# RSD_M1_HELMET_UNIT_MCU_STOP_LIGHT_V2.net
KiCad netlist of a schematic drawn in Altium Designer
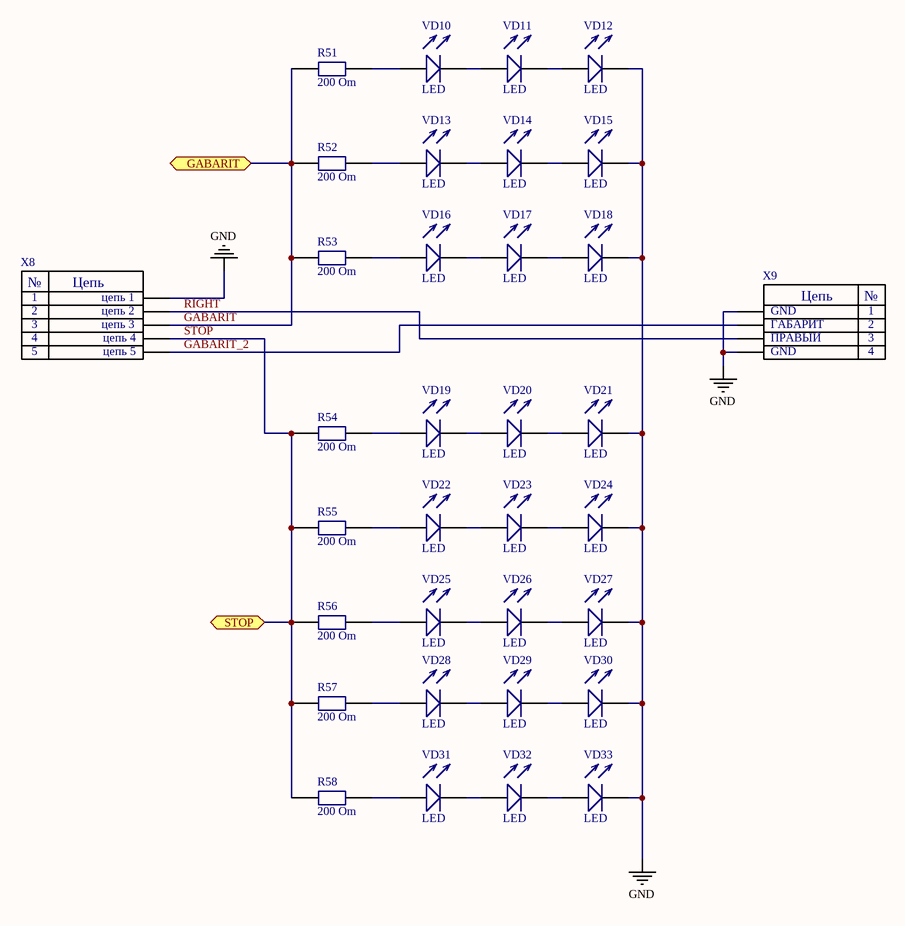
[diagram p0: RSD_M1_HELMET_UNIT_MCU_STOP_LIGHT_V2.SchDoc]

(export (version "E")
  (design (tool "Eeschema 10.0.6"))
  (components
    (comp (ref "R51")
      (value "200 Om")
      (footprint "Res0603")
      (fields (field (name "Comment") "Resistor"))
      (libsource (lib "my_library") (part "Resistor"))
    )
    (comp (ref "R52")
      (value "200 Om")
      (footprint "Res0603")
      (fields (field (name "Comment") "Resistor"))
      (libsource (lib "my_library") (part "Resistor"))
    )
    (comp (ref "R53")
      (value "200 Om")
      (footprint "Res0603")
      (fields (field (name "Comment") "Resistor"))
      (libsource (lib "my_library") (part "Resistor"))
    )
    (comp (ref "R54")
      (value "200 Om")
      (footprint "Res0603")
      (fields (field (name "Comment") "Resistor"))
      (libsource (lib "my_library") (part "Resistor"))
    )
    (comp (ref "R55")
      (value "200 Om")
      (footprint "Res0603")
      (fields (field (name "Comment") "Resistor"))
      (libsource (lib "my_library") (part "Resistor"))
    )
    (comp (ref "R56")
      (value "200 Om")
      (footprint "Res0603")
      (fields (field (name "Comment") "Resistor"))
      (libsource (lib "my_library") (part "Resistor"))
    )
    (comp (ref "R57")
      (value "200 Om")
      (footprint "Res0603")
      (fields (field (name "Comment") "Resistor"))
      (libsource (lib "my_library") (part "Resistor"))
    )
    (comp (ref "R58")
      (value "200 Om")
      (footprint "Res0603")
      (fields (field (name "Comment") "Resistor"))
      (libsource (lib "my_library") (part "Resistor"))
    )
    (comp (ref "VD10") (value "LED") (footprint "3528_LED") (libsource (lib "my_library") (part "LED")))
    (comp (ref "VD11") (value "LED") (footprint "3528_LED") (libsource (lib "my_library") (part "LED")))
    (comp (ref "VD12") (value "LED") (footprint "3528_LED") (libsource (lib "my_library") (part "LED")))
    (comp (ref "VD13") (value "LED") (footprint "3528_LED") (libsource (lib "my_library") (part "LED")))
    (comp (ref "VD14") (value "LED") (footprint "3528_LED") (libsource (lib "my_library") (part "LED")))
    (comp (ref "VD15") (value "LED") (footprint "3528_LED") (libsource (lib "my_library") (part "LED")))
    (comp (ref "VD16") (value "LED") (footprint "3528_LED") (libsource (lib "my_library") (part "LED")))
    (comp (ref "VD17") (value "LED") (footprint "3528_LED") (libsource (lib "my_library") (part "LED")))
    (comp (ref "VD18") (value "LED") (footprint "3528_LED") (libsource (lib "my_library") (part "LED")))
    (comp (ref "VD19") (value "LED") (footprint "3528_LED") (libsource (lib "my_library") (part "LED")))
    (comp (ref "VD20") (value "LED") (footprint "3528_LED") (libsource (lib "my_library") (part "LED")))
    (comp (ref "VD21") (value "LED") (footprint "3528_LED") (libsource (lib "my_library") (part "LED")))
    (comp (ref "VD22") (value "LED") (footprint "3528_LED") (libsource (lib "my_library") (part "LED")))
    (comp (ref "VD23") (value "LED") (footprint "3528_LED") (libsource (lib "my_library") (part "LED")))
    (comp (ref "VD24") (value "LED") (footprint "3528_LED") (libsource (lib "my_library") (part "LED")))
    (comp (ref "VD25") (value "LED") (footprint "3528_LED") (libsource (lib "my_library") (part "LED")))
    (comp (ref "VD26") (value "LED") (footprint "3528_LED") (libsource (lib "my_library") (part "LED")))
    (comp (ref "VD27") (value "LED") (footprint "3528_LED") (libsource (lib "my_library") (part "LED")))
    (comp (ref "VD28") (value "LED") (footprint "3528_LED") (libsource (lib "my_library") (part "LED")))
    (comp (ref "VD29") (value "LED") (footprint "3528_LED") (libsource (lib "my_library") (part "LED")))
    (comp (ref "VD30") (value "LED") (footprint "3528_LED") (libsource (lib "my_library") (part "LED")))
    (comp (ref "VD31") (value "LED") (footprint "3528_LED") (libsource (lib "my_library") (part "LED")))
    (comp (ref "VD32") (value "LED") (footprint "3528_LED") (libsource (lib "my_library") (part "LED")))
    (comp (ref "VD33") (value "LED") (footprint "3528_LED") (libsource (lib "my_library") (part "LED")))
    (comp (ref "X8")
      (value "FPC_connector_5_1")
      (footprint "FPC_5_1")
      (fields
        (field (name "1") "цепь 1")
        (field (name "2") "цепь 2")
        (field (name "3") "цепь 3")
        (field (name "4") "цепь 4")
        (field (name "5") "цепь 5")
      )
      (libsource (lib "my_library") (part "FPC_connector_5_1"))
    )
    (comp (ref "X9")
      (value "FPC_connector_4_1")
      (footprint "FPC_4_1")
      (fields
        (field (name "1") "GND")
        (field (name "2") "ГАБАРИТ")
        (field (name "3") "ПРАВЫЙ")
        (field (name "4") "GND")
      )
      (libsource (lib "my_library") (part "FPC_connector_4_1"))
    )
  )
  (nets
    (net (code "1") (name "/GABARIT") (class "Default")
      (node (ref "R51") (pin "2") (pinfunction "2_2") (pintype "passive"))
      (node (ref "R52") (pin "2") (pinfunction "2_2") (pintype "passive"))
      (node (ref "R53") (pin "2") (pinfunction "2_2") (pintype "passive"))
      (node (ref "X8") (pin "3") (pinfunction "3_3") (pintype "passive"))
    )
    (net (code "2") (name "/GABARIT_2") (class "Default")
      (node (ref "X8") (pin "5") (pinfunction "5_5") (pintype "passive"))
      (node (ref "X9") (pin "2") (pinfunction "2_2") (pintype "passive"))
    )
    (net (code "3") (name "/RIGHT") (class "Default")
      (node (ref "X8") (pin "2") (pinfunction "2_2") (pintype "passive"))
      (node (ref "X9") (pin "3") (pinfunction "3_3") (pintype "passive"))
    )
    (net (code "4") (name "/STOP") (class "Default")
      (node (ref "R54") (pin "2") (pinfunction "2_2") (pintype "passive"))
      (node (ref "R55") (pin "2") (pinfunction "2_2") (pintype "passive"))
      (node (ref "R56") (pin "2") (pinfunction "2_2") (pintype "passive"))
      (node (ref "R57") (pin "2") (pinfunction "2_2") (pintype "passive"))
      (node (ref "R58") (pin "2") (pinfunction "2_2") (pintype "passive"))
      (node (ref "X8") (pin "4") (pinfunction "4_4") (pintype "passive"))
    )
    (net (code "5") (name "GND") (class "Default")
      (node (ref "VD12") (pin "1") (pinfunction "1_1") (pintype "passive"))
      (node (ref "VD15") (pin "1") (pinfunction "1_1") (pintype "passive"))
      (node (ref "VD18") (pin "1") (pinfunction "1_1") (pintype "passive"))
      (node (ref "VD21") (pin "1") (pinfunction "1_1") (pintype "passive"))
      (node (ref "VD24") (pin "1") (pinfunction "1_1") (pintype "passive"))
      (node (ref "VD27") (pin "1") (pinfunction "1_1") (pintype "passive"))
      (node (ref "VD30") (pin "1") (pinfunction "1_1") (pintype "passive"))
      (node (ref "VD33") (pin "1") (pinfunction "1_1") (pintype "passive"))
      (node (ref "X8") (pin "1") (pinfunction "1_1") (pintype "passive"))
      (node (ref "X9") (pin "1") (pinfunction "1_1") (pintype "passive"))
      (node (ref "X9") (pin "4") (pinfunction "4_4") (pintype "passive"))
    )
    (net (code "6") (name "Net-(R51-Pad1)") (class "Default")
      (node (ref "R51") (pin "1") (pinfunction "1_1") (pintype "passive"))
      (node (ref "VD10") (pin "2") (pinfunction "2_2") (pintype "passive"))
    )
    (net (code "7") (name "Net-(R52-Pad1)") (class "Default")
      (node (ref "R52") (pin "1") (pinfunction "1_1") (pintype "passive"))
      (node (ref "VD13") (pin "2") (pinfunction "2_2") (pintype "passive"))
    )
    (net (code "8") (name "Net-(R53-Pad1)") (class "Default")
      (node (ref "R53") (pin "1") (pinfunction "1_1") (pintype "passive"))
      (node (ref "VD16") (pin "2") (pinfunction "2_2") (pintype "passive"))
    )
    (net (code "9") (name "Net-(R54-Pad1)") (class "Default")
      (node (ref "R54") (pin "1") (pinfunction "1_1") (pintype "passive"))
      (node (ref "VD19") (pin "2") (pinfunction "2_2") (pintype "passive"))
    )
    (net (code "10") (name "Net-(R55-Pad1)") (class "Default")
      (node (ref "R55") (pin "1") (pinfunction "1_1") (pintype "passive"))
      (node (ref "VD22") (pin "2") (pinfunction "2_2") (pintype "passive"))
    )
    (net (code "11") (name "Net-(R56-Pad1)") (class "Default")
      (node (ref "R56") (pin "1") (pinfunction "1_1") (pintype "passive"))
      (node (ref "VD25") (pin "2") (pinfunction "2_2") (pintype "passive"))
    )
    (net (code "12") (name "Net-(R57-Pad1)") (class "Default")
      (node (ref "R57") (pin "1") (pinfunction "1_1") (pintype "passive"))
      (node (ref "VD28") (pin "2") (pinfunction "2_2") (pintype "passive"))
    )
    (net (code "13") (name "Net-(R58-Pad1)") (class "Default")
      (node (ref "R58") (pin "1") (pinfunction "1_1") (pintype "passive"))
      (node (ref "VD31") (pin "2") (pinfunction "2_2") (pintype "passive"))
    )
    (net (code "14") (name "Net-(VD10-Pad1)") (class "Default")
      (node (ref "VD10") (pin "1") (pinfunction "1_1") (pintype "passive"))
      (node (ref "VD11") (pin "2") (pinfunction "2_2") (pintype "passive"))
    )
    (net (code "15") (name "Net-(VD11-Pad1)") (class "Default")
      (node (ref "VD11") (pin "1") (pinfunction "1_1") (pintype "passive"))
      (node (ref "VD12") (pin "2") (pinfunction "2_2") (pintype "passive"))
    )
    (net (code "16") (name "Net-(VD13-Pad1)") (class "Default")
      (node (ref "VD13") (pin "1") (pinfunction "1_1") (pintype "passive"))
      (node (ref "VD14") (pin "2") (pinfunction "2_2") (pintype "passive"))
    )
    (net (code "17") (name "Net-(VD14-Pad1)") (class "Default")
      (node (ref "VD14") (pin "1") (pinfunction "1_1") (pintype "passive"))
      (node (ref "VD15") (pin "2") (pinfunction "2_2") (pintype "passive"))
    )
    (net (code "18") (name "Net-(VD16-Pad1)") (class "Default")
      (node (ref "VD16") (pin "1") (pinfunction "1_1") (pintype "passive"))
      (node (ref "VD17") (pin "2") (pinfunction "2_2") (pintype "passive"))
    )
    (net (code "19") (name "Net-(VD17-Pad1)") (class "Default")
      (node (ref "VD17") (pin "1") (pinfunction "1_1") (pintype "passive"))
      (node (ref "VD18") (pin "2") (pinfunction "2_2") (pintype "passive"))
    )
    (net (code "20") (name "Net-(VD19-Pad1)") (class "Default")
      (node (ref "VD19") (pin "1") (pinfunction "1_1") (pintype "passive"))
      (node (ref "VD20") (pin "2") (pinfunction "2_2") (pintype "passive"))
    )
    (net (code "21") (name "Net-(VD20-Pad1)") (class "Default")
      (node (ref "VD20") (pin "1") (pinfunction "1_1") (pintype "passive"))
      (node (ref "VD21") (pin "2") (pinfunction "2_2") (pintype "passive"))
    )
    (net (code "22") (name "Net-(VD22-Pad1)") (class "Default")
      (node (ref "VD22") (pin "1") (pinfunction "1_1") (pintype "passive"))
      (node (ref "VD23") (pin "2") (pinfunction "2_2") (pintype "passive"))
    )
    (net (code "23") (name "Net-(VD23-Pad1)") (class "Default")
      (node (ref "VD23") (pin "1") (pinfunction "1_1") (pintype "passive"))
      (node (ref "VD24") (pin "2") (pinfunction "2_2") (pintype "passive"))
    )
    (net (code "24") (name "Net-(VD25-Pad1)") (class "Default")
      (node (ref "VD25") (pin "1") (pinfunction "1_1") (pintype "passive"))
      (node (ref "VD26") (pin "2") (pinfunction "2_2") (pintype "passive"))
    )
    (net (code "25") (name "Net-(VD26-Pad1)") (class "Default")
      (node (ref "VD26") (pin "1") (pinfunction "1_1") (pintype "passive"))
      (node (ref "VD27") (pin "2") (pinfunction "2_2") (pintype "passive"))
    )
    (net (code "26") (name "Net-(VD28-Pad1)") (class "Default")
      (node (ref "VD28") (pin "1") (pinfunction "1_1") (pintype "passive"))
      (node (ref "VD29") (pin "2") (pinfunction "2_2") (pintype "passive"))
    )
    (net (code "27") (name "Net-(VD29-Pad1)") (class "Default")
      (node (ref "VD29") (pin "1") (pinfunction "1_1") (pintype "passive"))
      (node (ref "VD30") (pin "2") (pinfunction "2_2") (pintype "passive"))
    )
    (net (code "28") (name "Net-(VD31-Pad1)") (class "Default")
      (node (ref "VD31") (pin "1") (pinfunction "1_1") (pintype "passive"))
      (node (ref "VD32") (pin "2") (pinfunction "2_2") (pintype "passive"))
    )
    (net (code "29") (name "Net-(VD32-Pad1)") (class "Default")
      (node (ref "VD32") (pin "1") (pinfunction "1_1") (pintype "passive"))
      (node (ref "VD33") (pin "2") (pinfunction "2_2") (pintype "passive"))
    )
  )
)
